# Power.net
KiCad netlist of a schematic drawn in Altium Designer
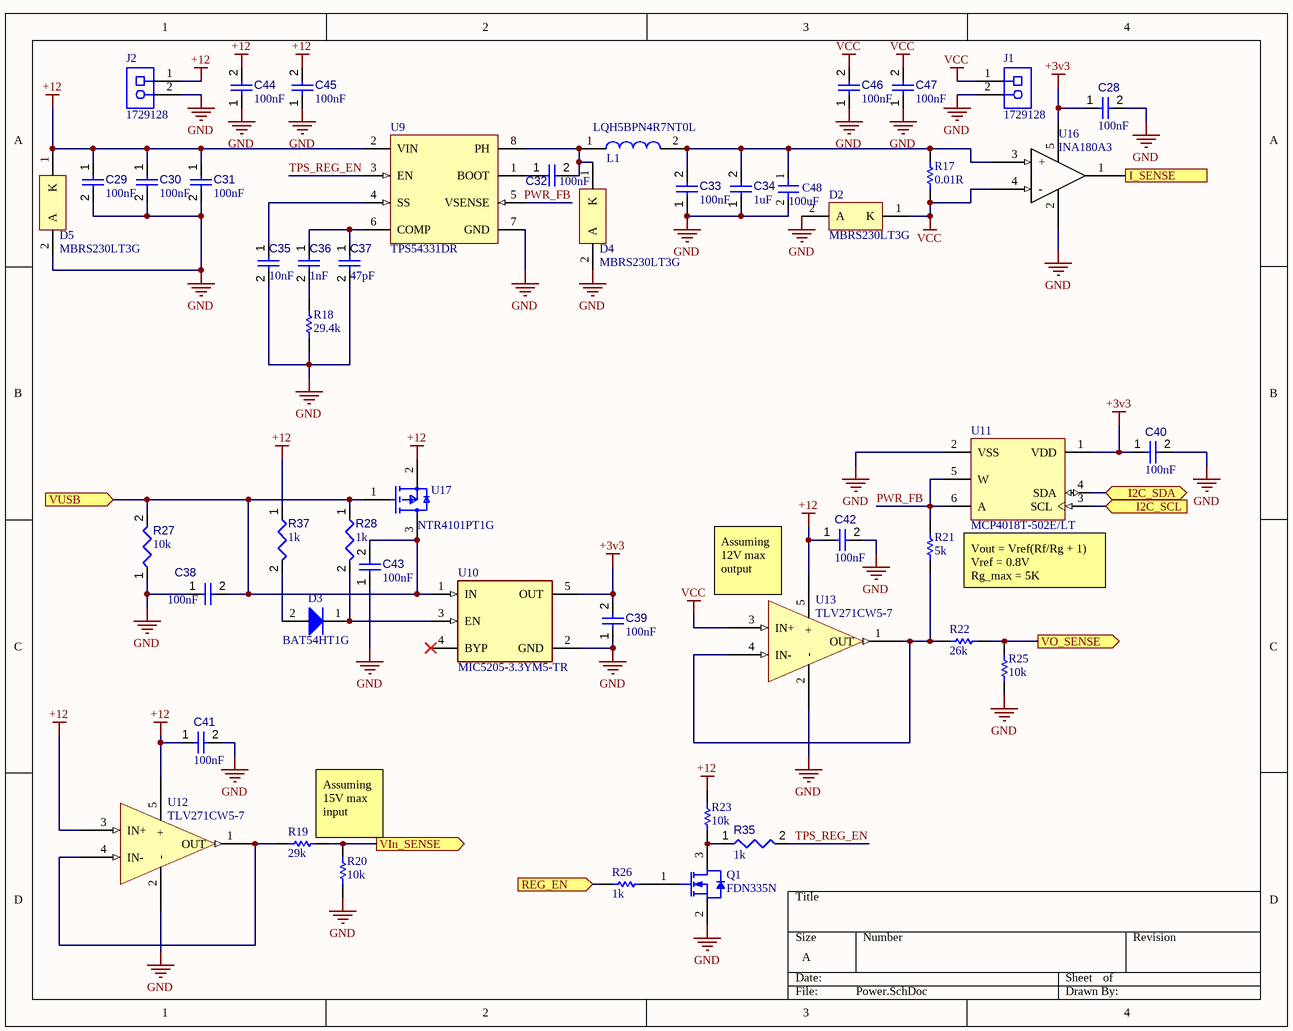
[diagram p0: Power.SchDoc]

(export (version "E")
  (design (tool "Eeschema 10.0.6"))
  (components
    (comp (ref "C28")
      (value "100nF")
      (footprint "CAPC2013X95X50ML10T25")
      (description "Chip Capacitor, 100 nF, +/- 10%, 50 V, 0805 (2012 Metric)")
      (fields (field (name "TOLERANCE") "10%") (field (name "Comment") "Capacitor 100 nF +/-10% 50 V 0805"))
      (libsource (lib "Aditya Sehgal") (part "CAP-NP-2"))
    )
    (comp (ref "C29")
      (value "100nF")
      (footprint "CAPC2013X95X50ML10T25")
      (description "Chip Capacitor, 100 nF, +/- 10%, 50 V, 0805 (2012 Metric)")
      (fields (field (name "TOLERANCE") "10%") (field (name "Comment") "Capacitor 100 nF +/-10% 50 V 0805"))
      (libsource (lib "Aditya Sehgal") (part "CAP-NP-2"))
    )
    (comp (ref "C30")
      (value "100nF")
      (footprint "CAPC2013X95X50ML10T25")
      (description "Chip Capacitor, 100 nF, +/- 10%, 50 V, 0805 (2012 Metric)")
      (fields (field (name "TOLERANCE") "10%") (field (name "Comment") "Capacitor 100 nF +/-10% 50 V 0805"))
      (libsource (lib "Aditya Sehgal") (part "CAP-NP-2"))
    )
    (comp (ref "C31")
      (value "100nF")
      (footprint "CAPC2013X95X50ML10T25")
      (description "Chip Capacitor, 100 nF, +/- 10%, 50 V, 0805 (2012 Metric)")
      (fields (field (name "TOLERANCE") "10%") (field (name "Comment") "Capacitor 100 nF +/-10% 50 V 0805"))
      (libsource (lib "Aditya Sehgal") (part "CAP-NP-2"))
    )
    (comp (ref "C32")
      (value "100nF")
      (footprint "CAPC2013X95X50ML10T25")
      (description "Chip Capacitor, 100 nF, +/- 10%, 50 V, 0805 (2012 Metric)")
      (fields (field (name "TOLERANCE") "10%") (field (name "Comment") "Capacitor 100 nF +/-10% 50 V 0805"))
      (libsource (lib "Aditya Sehgal") (part "CAP-NP-2"))
    )
    (comp (ref "C33")
      (value "100nF")
      (footprint "CAPC2013X95X50ML10T25")
      (description "Chip Capacitor, 100 nF, +/- 10%, 50 V, 0805 (2012 Metric)")
      (fields (field (name "TOLERANCE") "10%") (field (name "Comment") "Capacitor 100 nF +/-10% 50 V 0805"))
      (libsource (lib "Aditya Sehgal") (part "CAP-NP-2"))
    )
    (comp (ref "C34")
      (value "1uF")
      (footprint "CAPC2013X95X50ML10T25")
      (description "Chip Capacitor, 100 nF, +/- 10%, 50 V, 0805 (2012 Metric)")
      (fields (field (name "TOLERANCE") "10%") (field (name "Comment") "Capacitor 100 nF +/-10% 50 V 0805"))
      (libsource (lib "Aditya Sehgal") (part "CAP-NP-2"))
    )
    (comp (ref "C35")
      (value "10nF")
      (footprint "CAPC2013X95X50ML10T25")
      (description "Chip Capacitor, 100 nF, +/- 10%, 50 V, 0805 (2012 Metric)")
      (fields (field (name "TOLERANCE") "10%") (field (name "Comment") "Capacitor 100 nF +/-10% 50 V 0805"))
      (libsource (lib "Aditya Sehgal") (part "CAP-NP-2"))
    )
    (comp (ref "C36")
      (value "1nF")
      (footprint "CAPC2013X95X50ML10T25")
      (description "Chip Capacitor, 100 nF, +/- 10%, 50 V, 0805 (2012 Metric)")
      (fields (field (name "TOLERANCE") "10%") (field (name "Comment") "Capacitor 100 nF +/-10% 50 V 0805"))
      (libsource (lib "Aditya Sehgal") (part "CAP-NP-2"))
    )
    (comp (ref "C37")
      (value "47pF")
      (footprint "CAPC2013X95X50ML10T25")
      (description "Chip Capacitor, 100 nF, +/- 10%, 50 V, 0805 (2012 Metric)")
      (fields (field (name "TOLERANCE") "10%") (field (name "Comment") "Capacitor 100 nF +/-10% 50 V 0805"))
      (libsource (lib "Aditya Sehgal") (part "CAP-NP-2"))
    )
    (comp (ref "C38")
      (value "100nF")
      (footprint "CAPC2013X95X50ML10T25")
      (description "Chip Capacitor, 100 nF, +/- 10%, 50 V, 0805 (2012 Metric)")
      (fields (field (name "TOLERANCE") "10%") (field (name "Comment") "Capacitor 100 nF +/-10% 50 V 0805"))
      (libsource (lib "Aditya Sehgal") (part "CAP-NP-2"))
    )
    (comp (ref "C39")
      (value "100nF")
      (footprint "CAPC2013X95X50ML10T25")
      (description "Chip Capacitor, 100 nF, +/- 10%, 50 V, 0805 (2012 Metric)")
      (fields (field (name "TOLERANCE") "10%") (field (name "Comment") "Capacitor 100 nF +/-10% 50 V 0805"))
      (libsource (lib "Aditya Sehgal") (part "CAP-NP-2"))
    )
    (comp (ref "C40")
      (value "100nF")
      (footprint "CAPC2013X95X50ML10T25")
      (description "Chip Capacitor, 100 nF, +/- 10%, 50 V, 0805 (2012 Metric)")
      (fields (field (name "TOLERANCE") "10%") (field (name "Comment") "Capacitor 100 nF +/-10% 50 V 0805"))
      (libsource (lib "Aditya Sehgal") (part "CAP-NP-2"))
    )
    (comp (ref "C41")
      (value "100nF")
      (footprint "CAPC2013X95X50ML10T25")
      (description "Chip Capacitor, 100 nF, +/- 10%, 50 V, 0805 (2012 Metric)")
      (fields (field (name "TOLERANCE") "10%") (field (name "Comment") "Capacitor 100 nF +/-10% 50 V 0805"))
      (libsource (lib "Aditya Sehgal") (part "CAP-NP-2"))
    )
    (comp (ref "C42")
      (value "100nF")
      (footprint "CAPC2013X95X50ML10T25")
      (description "Chip Capacitor, 100 nF, +/- 10%, 50 V, 0805 (2012 Metric)")
      (fields (field (name "TOLERANCE") "10%") (field (name "Comment") "Capacitor 100 nF +/-10% 50 V 0805"))
      (libsource (lib "Aditya Sehgal") (part "CAP-NP-2"))
    )
    (comp (ref "C43")
      (value "100nF")
      (footprint "CAPC0805(2012)145_L")
      (description "Chip Capacitor, 100µF +/-20%, 6.3V, 0805, Thickness 1.45 mm")
      (fields (field (name "TOLERANCE") "10%") (field (name "Comment") "Capacitor 100µF +/-20% 6.3V 0805"))
      (libsource (lib "University of California Santa Cruz") (part "CAP-NP-2"))
    )
    (comp (ref "C44")
      (value "100nF")
      (footprint "CAPC2013X95X50LL10T25")
      (description "Chip Capacitor, 100 nF, +/- 10%, 50 V, 0805 (2012 Metric)")
      (fields (field (name "TOLERANCE") "10%") (field (name "Comment") "Capacitor 100 nF +/-10% 50 V 0805"))
      (libsource (lib "University of California Santa Cruz") (part "CAP-NP-2"))
    )
    (comp (ref "C45")
      (value "100nF")
      (footprint "CAPC2013X95X50LL10T25")
      (description "Chip Capacitor, 100 nF, +/- 10%, 50 V, 0805 (2012 Metric)")
      (fields (field (name "TOLERANCE") "10%") (field (name "Comment") "Capacitor 100 nF +/-10% 50 V 0805"))
      (libsource (lib "University of California Santa Cruz") (part "CAP-NP-2"))
    )
    (comp (ref "C46")
      (value "100nF")
      (footprint "CAPC2013X95X50LL10T25")
      (description "Chip Capacitor, 100 nF, +/- 10%, 50 V, 0805 (2012 Metric)")
      (fields (field (name "TOLERANCE") "10%") (field (name "Comment") "Capacitor 100 nF +/-10% 50 V 0805"))
      (libsource (lib "University of California Santa Cruz") (part "CAP-NP-2"))
    )
    (comp (ref "C47")
      (value "100nF")
      (footprint "CAPC2013X95X50LL10T25")
      (description "Chip Capacitor, 100 nF, +/- 10%, 50 V, 0805 (2012 Metric)")
      (fields (field (name "TOLERANCE") "10%") (field (name "Comment") "Capacitor 100 nF +/-10% 50 V 0805"))
      (libsource (lib "University of California Santa Cruz") (part "CAP-NP-2"))
    )
    (comp (ref "C48")
      (value "100uF")
      (footprint "CKG57NX7S1C107M-Footprint-1")
      (description "100uF 16V Stacked MLCC\r\nCKG57NX7S1C107M")
      (libsource (lib "Knightscope, Inc") (part "CKG57NZ7S1C107M"))
    )
    (comp (ref "D2")
      (value "MBRS230LT3G")
      (footprint "ONSC-SMB-2-403A-03_D_V")
      (description "Schottky Power Rectifier, 2-Pin SMB, Pb-Free, Tape and Reel")
      (fields (field (name "MANUFACTURER") "On Semiconductor"))
      (libsource (lib "") (part "ONSC-D-K1A2-2_A_1"))
    )
    (comp (ref "D3")
      (value "BAT54HT1G")
      (footprint "ONSC-SOD-323-2-477-02_V")
      (description "Schottky Barrier Diode, 2-Pin SOD-323, Pb-Free, Tape and Reel")
      (fields (field (name "MANUFACTURER") "On Semiconductor"))
      (libsource (lib "Altium Content Vault") (part "ONSC-D-K1A2-2"))
    )
    (comp (ref "D4")
      (value "MBRS230LT3G")
      (footprint "ONSC-SMB-2-403A-03_D_V")
      (description "Schottky Power Rectifier, 2-Pin SMB, Pb-Free, Tape and Reel")
      (fields (field (name "MANUFACTURER") "On Semiconductor"))
      (libsource (lib "Altium Content Vault") (part "ONSC-D-K1A2-2_A"))
    )
    (comp (ref "D5")
      (value "MBRS230LT3G")
      (footprint "ONSC-SMB-2-403A-03_D_V")
      (description "Schottky Power Rectifier, 2-Pin SMB, Pb-Free, Tape and Reel")
      (fields (field (name "MANUFACTURER") "On Semiconductor"))
      (libsource (lib "Altium Content Vault") (part "ONSC-D-K1A2-2_A"))
    )
    (comp (ref "J1")
      (value "1729128")
      (footprint "PHOE-1729128-2_V")
      (description "PCB Terminal Block, 13.5 A, 400 V, 2-Pin THD, RoHS, Bulk")
      (fields (field (name "MANUFACTURER") "Phoenix Contact"))
      (libsource (lib "") (part "CN-2P-F-R2_1"))
    )
    (comp (ref "J2")
      (value "1729128")
      (footprint "PHOE-1729128-2_V")
      (description "PCB Terminal Block, 13.5 A, 400 V, 2-Pin THD, RoHS, Bulk")
      (fields (field (name "MANUFACTURER") "Phoenix Contact"))
      (libsource (lib "Altium Content Vault") (part "CN-2P-F-R2"))
    )
    (comp (ref "L1")
      (value "LQH5BPN4R7NT0L")
      (footprint "LQH5BPN4R7NT0L-Footprint-1")
      (description "4.7uH 2A 58mOhm 5x5mm inductor Murata")
      (libsource (lib "Aditya Sehgal") (part "LQH5BPN4R7NT0L"))
    )
    (comp (ref "Q1")
      (value "FDN335N")
      (footprint "FAIR-SSOT3L-3_V")
      (fields (field (name "MANUFACTURER") "FairchildSemiconductor"))
      (libsource (lib "Altium Content Vault") (part "NEMOS-GSD-3"))
    )
    (comp (ref "R17")
      (value "0.01R")
      (footprint "RESC3216X60X45ML15T20")
      (description "Chip Resistor, 0 Ohm, +/- 5%, 0.25 W, -55 to 155 degC, 1206 (3216 Metric)")
      (fields (field (name "POWER") "250mW") (field (name "TOLERANCE") "5%"))
      (libsource (lib "Aditya Sehgal") (part "RES-2"))
    )
    (comp (ref "R18")
      (value "29.4k")
      (footprint "RESC2013X50X35ML15T15")
      (description "Chip Resistor, 0 Ohm, +/- 1%, 125 mW, -55 to 155 degC, 0805 (2012 Metric)")
      (fields (field (name "TOLERANCE") "1%") (field (name "POWER") "125mW"))
      (libsource (lib "Aditya Sehgal") (part "RES-2"))
    )
    (comp (ref "R19")
      (value "29k")
      (footprint "RESC2013X50X35ML15T15")
      (description "Chip Resistor, 0 Ohm, +/- 1%, 125 mW, -55 to 155 degC, 0805 (2012 Metric)")
      (fields (field (name "TOLERANCE") "1%") (field (name "POWER") "125mW"))
      (libsource (lib "Aditya Sehgal") (part "RES-2"))
    )
    (comp (ref "R20")
      (value "10k")
      (footprint "RESC2013X50X35ML15T15")
      (description "Chip Resistor, 0 Ohm, +/- 1%, 125 mW, -55 to 155 degC, 0805 (2012 Metric)")
      (fields (field (name "TOLERANCE") "1%") (field (name "POWER") "125mW"))
      (libsource (lib "Aditya Sehgal") (part "RES-2"))
    )
    (comp (ref "R21")
      (value "5k")
      (footprint "RESC2013X50X35ML15T15")
      (description "Chip Resistor, 0 Ohm, +/- 1%, 125 mW, -55 to 155 degC, 0805 (2012 Metric)")
      (fields (field (name "TOLERANCE") "1%") (field (name "POWER") "125mW"))
      (libsource (lib "Aditya Sehgal") (part "RES-2"))
    )
    (comp (ref "R22")
      (value "26k")
      (footprint "RESC2013X50X35ML15T15")
      (description "Chip Resistor, 0 Ohm, +/- 1%, 125 mW, -55 to 155 degC, 0805 (2012 Metric)")
      (fields (field (name "TOLERANCE") "1%") (field (name "POWER") "125mW"))
      (libsource (lib "Aditya Sehgal") (part "RES-2"))
    )
    (comp (ref "R23")
      (value "10k")
      (footprint "RESC2013X50X35ML15T15")
      (description "Chip Resistor, 0 Ohm, +/- 1%, 125 mW, -55 to 155 degC, 0805 (2012 Metric)")
      (fields (field (name "TOLERANCE") "1%") (field (name "POWER") "125mW"))
      (libsource (lib "Aditya Sehgal") (part "RES-2"))
    )
    (comp (ref "R25")
      (value "10k")
      (footprint "RESC2013X50X35ML15T15")
      (description "Chip Resistor, 0 Ohm, +/- 1%, 125 mW, -55 to 155 degC, 0805 (2012 Metric)")
      (fields (field (name "TOLERANCE") "1%") (field (name "POWER") "125mW"))
      (libsource (lib "Aditya Sehgal") (part "RES-2"))
    )
    (comp (ref "R26")
      (value "1k")
      (footprint "RESC2013X50X35ML15T15")
      (description "Chip Resistor, 0 Ohm, +/- 1%, 125 mW, -55 to 155 degC, 0805 (2012 Metric)")
      (fields (field (name "TOLERANCE") "1%") (field (name "POWER") "125mW"))
      (libsource (lib "Aditya Sehgal") (part "RES-2"))
    )
    (comp (ref "R27")
      (value "10k")
      (footprint "RESC2013X50X35ML15T15")
      (description "Chip Resistor, 10 KOhm, +/- 1%, 125 mW, -55 to 155 degC, 0805 (2012 Metric)")
      (fields (field (name "POWER") "125mW") (field (name "TOLERANCE") "1%"))
      (libsource (lib "University of California Santa Cruz") (part "RES-2"))
    )
    (comp (ref "R28")
      (value "1k")
      (footprint "RESC2013X50X35ML15T15")
      (description "Chip Resistor, 10 KOhm, +/- 1%, 125 mW, -55 to 155 degC, 0805 (2012 Metric)")
      (fields (field (name "POWER") "125mW") (field (name "TOLERANCE") "1%"))
      (libsource (lib "University of California Santa Cruz") (part "RES-2"))
    )
    (comp (ref "R35")
      (value "1k")
      (footprint "RESC2013X50X35ML15T15")
      (description "Chip Resistor, 10 KOhm, +/- 1%, 125 mW, -55 to 155 degC, 0805 (2012 Metric)")
      (fields (field (name "POWER") "125mW") (field (name "TOLERANCE") "1%"))
      (libsource (lib "University of California Santa Cruz") (part "RES-2"))
    )
    (comp (ref "R37")
      (value "1k")
      (footprint "RESC2013X50X35ML15T15")
      (description "Chip Resistor, 10 KOhm, +/- 1%, 125 mW, -55 to 155 degC, 0805 (2012 Metric)")
      (fields (field (name "POWER") "125mW") (field (name "TOLERANCE") "1%"))
      (libsource (lib "University of California Santa Cruz") (part "RES-2"))
    )
    (comp (ref "U9")
      (value "TPS54331DR")
      (footprint "D0008A_L")
      (fields (field (name "MANUFACTURER") "Texas Instruments"))
      (libsource (lib "Altium Content Vault") (part "TI-TPS54331D8"))
    )
    (comp (ref "U10")
      (value "MIC5205-3.3YM5-TR")
      (footprint "FP-M5-IPC_C")
      (description "IC REG LINEAR 3.3V 150MA SOT23-5")
      (fields
        (field (name "MANUFACTURER") "Microchip")
        (field (name "OCTOPART") "https://octopart.com/mic5205-3.3ym5-tr-microchip-66802130")
      )
      (libsource (lib "Altium Content Vault") (part "b2bb7f462d557aec50a251fc6568b2e"))
    )
    (comp (ref "U11")
      (value "MCP4018T-502E/LT")
      (footprint "SC70-LT6_L")
      (description "7-Bit Single I2C Digital POT with Volatile Memory, 6-pin SC70, Extended Temperature, Tape and Reel")
      (libsource (lib "Altium Content Vault") (part "IN-DPOT-MCP4018-6"))
    )
    (comp (ref "U12")
      (value "TLV271CW5-7")
      (footprint "SOT95P285X130-5N")
      (description "IC OPAMP GP 3MHZ RRO SOT25")
      (libsource (lib "University of California Santa Cruz") (part "TLV271CW5-7"))
    )
    (comp (ref "U13")
      (value "TLV271CW5-7")
      (footprint "SOT95P285X130-5N")
      (description "IC OPAMP GP 3MHZ RRO SOT25")
      (libsource (lib "University of California Santa Cruz") (part "TLV271CW5-7"))
    )
    (comp (ref "U16")
      (value "INA180A3")
      (footprint "SOT95P245X110-5N")
      (description "Current Sense Amplifier 100V/V")
      (libsource (lib "Aditya Sehgal") (part "INA180A3"))
    )
    (comp (ref "U17")
      (value "NTR4101PT1G")
      (footprint "FP-318-08-MFG")
      (description "MOSFET P-CH 20V 1.8A SOT-23")
      (libsource (lib "Altium Content Vault") (part "d54a8bb486e18a944bb8606ec07e2b8"))
    )
  )
  (nets
    (net (code "1") (name "+3v3") (class "Default")
      (node (ref "C28") (pin "1") (pinfunction "1_1") (pintype "passive"))
      (node (ref "C39") (pin "2") (pinfunction "2_2") (pintype "passive"))
      (node (ref "C40") (pin "1") (pinfunction "1_1") (pintype "passive"))
      (node (ref "U10") (pin "5") (pinfunction "OUT_5") (pintype "power_in"))
      (node (ref "U11") (pin "1") (pinfunction "VDD_1") (pintype "power_in"))
      (node (ref "U16") (pin "5") (pinfunction "Vcc_5") (pintype "passive"))
    )
    (net (code "2") (name "+12") (class "Default")
      (node (ref "C29") (pin "1") (pinfunction "1_1") (pintype "passive"))
      (node (ref "C30") (pin "1") (pinfunction "1_1") (pintype "passive"))
      (node (ref "C31") (pin "1") (pinfunction "1_1") (pintype "passive"))
      (node (ref "C41") (pin "1") (pinfunction "1_1") (pintype "passive"))
      (node (ref "C42") (pin "1") (pinfunction "1_1") (pintype "passive"))
      (node (ref "C44") (pin "2") (pinfunction "2_2") (pintype "passive"))
      (node (ref "C45") (pin "2") (pinfunction "2_2") (pintype "passive"))
      (node (ref "D5") (pin "1") (pinfunction "K_1") (pintype "passive"))
      (node (ref "J2") (pin "1") (pinfunction "1_1") (pintype "passive"))
      (node (ref "R23") (pin "2") (pinfunction "2_2") (pintype "passive"))
      (node (ref "R37") (pin "1") (pinfunction "1_1") (pintype "passive"))
      (node (ref "U12") (pin "3") (pinfunction "IN+_3") (pintype "input"))
      (node (ref "U12") (pin "5") (pinfunction "+_5") (pintype "power_in"))
      (node (ref "U13") (pin "5") (pinfunction "+_5") (pintype "power_in"))
      (node (ref "U17") (pin "2") (pinfunction "Source_2") (pintype "passive"))
      (node (ref "U9") (pin "2") (pinfunction "VIN_2") (pintype "power_in"))
    )
    (net (code "3") (name "/I2C_SCL") (class "Default")
      (node (ref "U11") (pin "3") (pinfunction "SCL_3") (pintype "input"))
    )
    (net (code "4") (name "/I2C_SDA") (class "Default")
      (node (ref "U11") (pin "4") (pinfunction "SDA_4") (pintype "bidirectional"))
    )
    (net (code "5") (name "/I_SENSE") (class "Default")
      (node (ref "U16") (pin "1") (pinfunction "out_1") (pintype "passive"))
    )
    (net (code "6") (name "/PWR_FB") (class "Default")
      (node (ref "R21") (pin "2") (pinfunction "2_2") (pintype "passive"))
      (node (ref "U11") (pin "5") (pinfunction "W_5") (pintype "passive"))
      (node (ref "U11") (pin "6") (pinfunction "A_6") (pintype "passive"))
      (node (ref "U9") (pin "5") (pinfunction "VSENSE_5") (pintype "input"))
    )
    (net (code "7") (name "/REG_EN") (class "Default")
      (node (ref "R26") (pin "1") (pinfunction "1_1") (pintype "passive"))
    )
    (net (code "8") (name "/TPS_REG_EN") (class "Default")
      (node (ref "R35") (pin "2") (pinfunction "2_2") (pintype "passive"))
      (node (ref "U9") (pin "3") (pinfunction "EN_3") (pintype "input"))
    )
    (net (code "9") (name "/VIn_SENSE") (class "Default")
      (node (ref "R19") (pin "2") (pinfunction "2_2") (pintype "passive"))
      (node (ref "R20") (pin "2") (pinfunction "2_2") (pintype "passive"))
    )
    (net (code "10") (name "/VO_SENSE") (class "Default")
      (node (ref "R22") (pin "2") (pinfunction "2_2") (pintype "passive"))
      (node (ref "R25") (pin "2") (pinfunction "2_2") (pintype "passive"))
    )
    (net (code "11") (name "/VUSB") (class "Default")
      (node (ref "C38") (pin "2") (pinfunction "2_2") (pintype "passive"))
      (node (ref "C43") (pin "2") (pinfunction "2_2") (pintype "passive"))
      (node (ref "R27") (pin "2") (pinfunction "2_2") (pintype "passive"))
      (node (ref "R28") (pin "1") (pinfunction "1_1") (pintype "passive"))
      (node (ref "U10") (pin "1") (pinfunction "IN_1") (pintype "input"))
      (node (ref "U17") (pin "1") (pinfunction "Gate_1") (pintype "passive"))
      (node (ref "U17") (pin "3") (pinfunction "Drain_3") (pintype "passive"))
    )
    (net (code "12") (name "GND") (class "Default")
      (node (ref "C28") (pin "2") (pinfunction "2_2") (pintype "passive"))
      (node (ref "C29") (pin "2") (pinfunction "2_2") (pintype "passive"))
      (node (ref "C30") (pin "2") (pinfunction "2_2") (pintype "passive"))
      (node (ref "C31") (pin "2") (pinfunction "2_2") (pintype "passive"))
      (node (ref "C33") (pin "1") (pinfunction "1_1") (pintype "passive"))
      (node (ref "C34") (pin "1") (pinfunction "1_1") (pintype "passive"))
      (node (ref "C35") (pin "2") (pinfunction "2_2") (pintype "passive"))
      (node (ref "C37") (pin "2") (pinfunction "2_2") (pintype "passive"))
      (node (ref "C38") (pin "1") (pinfunction "1_1") (pintype "passive"))
      (node (ref "C39") (pin "1") (pinfunction "1_1") (pintype "passive"))
      (node (ref "C40") (pin "2") (pinfunction "2_2") (pintype "passive"))
      (node (ref "C41") (pin "2") (pinfunction "2_2") (pintype "passive"))
      (node (ref "C42") (pin "2") (pinfunction "2_2") (pintype "passive"))
      (node (ref "C43") (pin "1") (pinfunction "1_1") (pintype "passive"))
      (node (ref "C44") (pin "1") (pinfunction "1_1") (pintype "passive"))
      (node (ref "C45") (pin "1") (pinfunction "1_1") (pintype "passive"))
      (node (ref "C46") (pin "1") (pinfunction "1_1") (pintype "passive"))
      (node (ref "C47") (pin "1") (pinfunction "1_1") (pintype "passive"))
      (node (ref "C48") (pin "2") (pinfunction "2_2") (pintype "passive"))
      (node (ref "D2") (pin "2") (pinfunction "A_2") (pintype "passive"))
      (node (ref "D4") (pin "2") (pinfunction "A_2") (pintype "passive"))
      (node (ref "D5") (pin "2") (pinfunction "A_2") (pintype "passive"))
      (node (ref "J1") (pin "2") (pinfunction "2_2") (pintype "passive"))
      (node (ref "J2") (pin "2") (pinfunction "2_2") (pintype "passive"))
      (node (ref "Q1") (pin "2") (pinfunction "S_2") (pintype "passive"))
      (node (ref "R18") (pin "2") (pinfunction "2_2") (pintype "passive"))
      (node (ref "R20") (pin "1") (pinfunction "1_1") (pintype "passive"))
      (node (ref "R25") (pin "1") (pinfunction "1_1") (pintype "passive"))
      (node (ref "R27") (pin "1") (pinfunction "1_1") (pintype "passive"))
      (node (ref "U10") (pin "2") (pinfunction "GND_2") (pintype "power_in"))
      (node (ref "U11") (pin "2") (pinfunction "VSS_2") (pintype "power_in"))
      (node (ref "U12") (pin "2") (pinfunction "-_2") (pintype "power_in"))
      (node (ref "U13") (pin "2") (pinfunction "-_2") (pintype "power_in"))
      (node (ref "U16") (pin "2") (pinfunction "GND_2") (pintype "power_in"))
      (node (ref "U9") (pin "7") (pinfunction "GND_7") (pintype "power_in"))
    )
    (net (code "13") (name "Net-(C36-Pad2)") (class "Default")
      (node (ref "C36") (pin "2") (pinfunction "2_2") (pintype "passive"))
      (node (ref "R18") (pin "1") (pinfunction "1_1") (pintype "passive"))
    )
    (net (code "14") (name "Net-(D3-A)") (class "Default")
      (node (ref "D3") (pin "2") (pinfunction "A_2") (pintype "passive"))
      (node (ref "R37") (pin "2") (pinfunction "2_2") (pintype "passive"))
    )
    (net (code "15") (name "Net-(D3-K)") (class "Default")
      (node (ref "D3") (pin "1") (pinfunction "K_1") (pintype "passive"))
      (node (ref "R28") (pin "2") (pinfunction "2_2") (pintype "passive"))
      (node (ref "U10") (pin "3") (pinfunction "EN_3") (pintype "input"))
    )
    (net (code "16") (name "Net-(D4-K)") (class "Default")
      (node (ref "C32") (pin "2") (pinfunction "2_2") (pintype "passive"))
      (node (ref "D4") (pin "1") (pinfunction "K_1") (pintype "passive"))
      (node (ref "L1") (pin "1") (pinfunction "7_1") (pintype "passive"))
      (node (ref "U9") (pin "8") (pinfunction "PH_8") (pintype "power_in"))
    )
    (net (code "17") (name "Net-(L1-8)") (class "Default")
      (node (ref "C33") (pin "2") (pinfunction "2_2") (pintype "passive"))
      (node (ref "C34") (pin "2") (pinfunction "2_2") (pintype "passive"))
      (node (ref "C48") (pin "1") (pinfunction "1_1") (pintype "open_emitter"))
      (node (ref "L1") (pin "2") (pinfunction "8_2") (pintype "passive"))
      (node (ref "R17") (pin "2") (pinfunction "2_2") (pintype "passive"))
      (node (ref "U16") (pin "3") (pinfunction "+_3") (pintype "input"))
    )
    (net (code "18") (name "Net-(Q1-D)") (class "Default")
      (node (ref "Q1") (pin "3") (pinfunction "D_3") (pintype "passive"))
      (node (ref "R23") (pin "1") (pinfunction "1_1") (pintype "passive"))
      (node (ref "R35") (pin "1") (pinfunction "1_1") (pintype "passive"))
    )
    (net (code "19") (name "Net-(Q1-G)") (class "Default")
      (node (ref "Q1") (pin "1") (pinfunction "G_1") (pintype "passive"))
      (node (ref "R26") (pin "2") (pinfunction "2_2") (pintype "passive"))
    )
    (net (code "20") (name "Net-(U9-BOOT)") (class "Default")
      (node (ref "C32") (pin "1") (pinfunction "1_1") (pintype "passive"))
      (node (ref "U9") (pin "1") (pinfunction "BOOT_1") (pintype "passive"))
    )
    (net (code "21") (name "Net-(U9-COMP)") (class "Default")
      (node (ref "C36") (pin "1") (pinfunction "1_1") (pintype "passive"))
      (node (ref "C37") (pin "1") (pinfunction "1_1") (pintype "passive"))
      (node (ref "U9") (pin "6") (pinfunction "COMP_6") (pintype "passive"))
    )
    (net (code "22") (name "Net-(U9-SS)") (class "Default")
      (node (ref "C35") (pin "1") (pinfunction "1_1") (pintype "passive"))
      (node (ref "U9") (pin "4") (pinfunction "SS_4") (pintype "input"))
    )
    (net (code "23") (name "Net-(U12-IN-)") (class "Default")
      (node (ref "R19") (pin "1") (pinfunction "1_1") (pintype "passive"))
      (node (ref "U12") (pin "1") (pinfunction "OUT_1") (pintype "output"))
      (node (ref "U12") (pin "4") (pinfunction "IN-_4") (pintype "input"))
    )
    (net (code "24") (name "Net-(U13-IN-)") (class "Default")
      (node (ref "R21") (pin "1") (pinfunction "1_1") (pintype "passive"))
      (node (ref "R22") (pin "1") (pinfunction "1_1") (pintype "passive"))
      (node (ref "U13") (pin "1") (pinfunction "OUT_1") (pintype "output"))
      (node (ref "U13") (pin "4") (pinfunction "IN-_4") (pintype "input"))
    )
    (net (code "25") (name "VCC") (class "Default")
      (node (ref "C46") (pin "2") (pinfunction "2_2") (pintype "passive"))
      (node (ref "C47") (pin "2") (pinfunction "2_2") (pintype "passive"))
      (node (ref "D2") (pin "1") (pinfunction "K_1") (pintype "passive"))
      (node (ref "J1") (pin "1") (pinfunction "1_1") (pintype "passive"))
      (node (ref "R17") (pin "1") (pinfunction "1_1") (pintype "passive"))
      (node (ref "U13") (pin "3") (pinfunction "IN+_3") (pintype "input"))
      (node (ref "U16") (pin "4") (pinfunction "-_4") (pintype "input"))
    )
    (net (code "26") (name "unconnected-(U10-BYP-Pad4)") (class "Default")
      (node (ref "U10") (pin "4") (pinfunction "BYP_4") (pintype "passive+no_connect"))
    )
  )
)
